# NixieMainboard.net
KiCad netlist of a schematic drawn in EAGLE
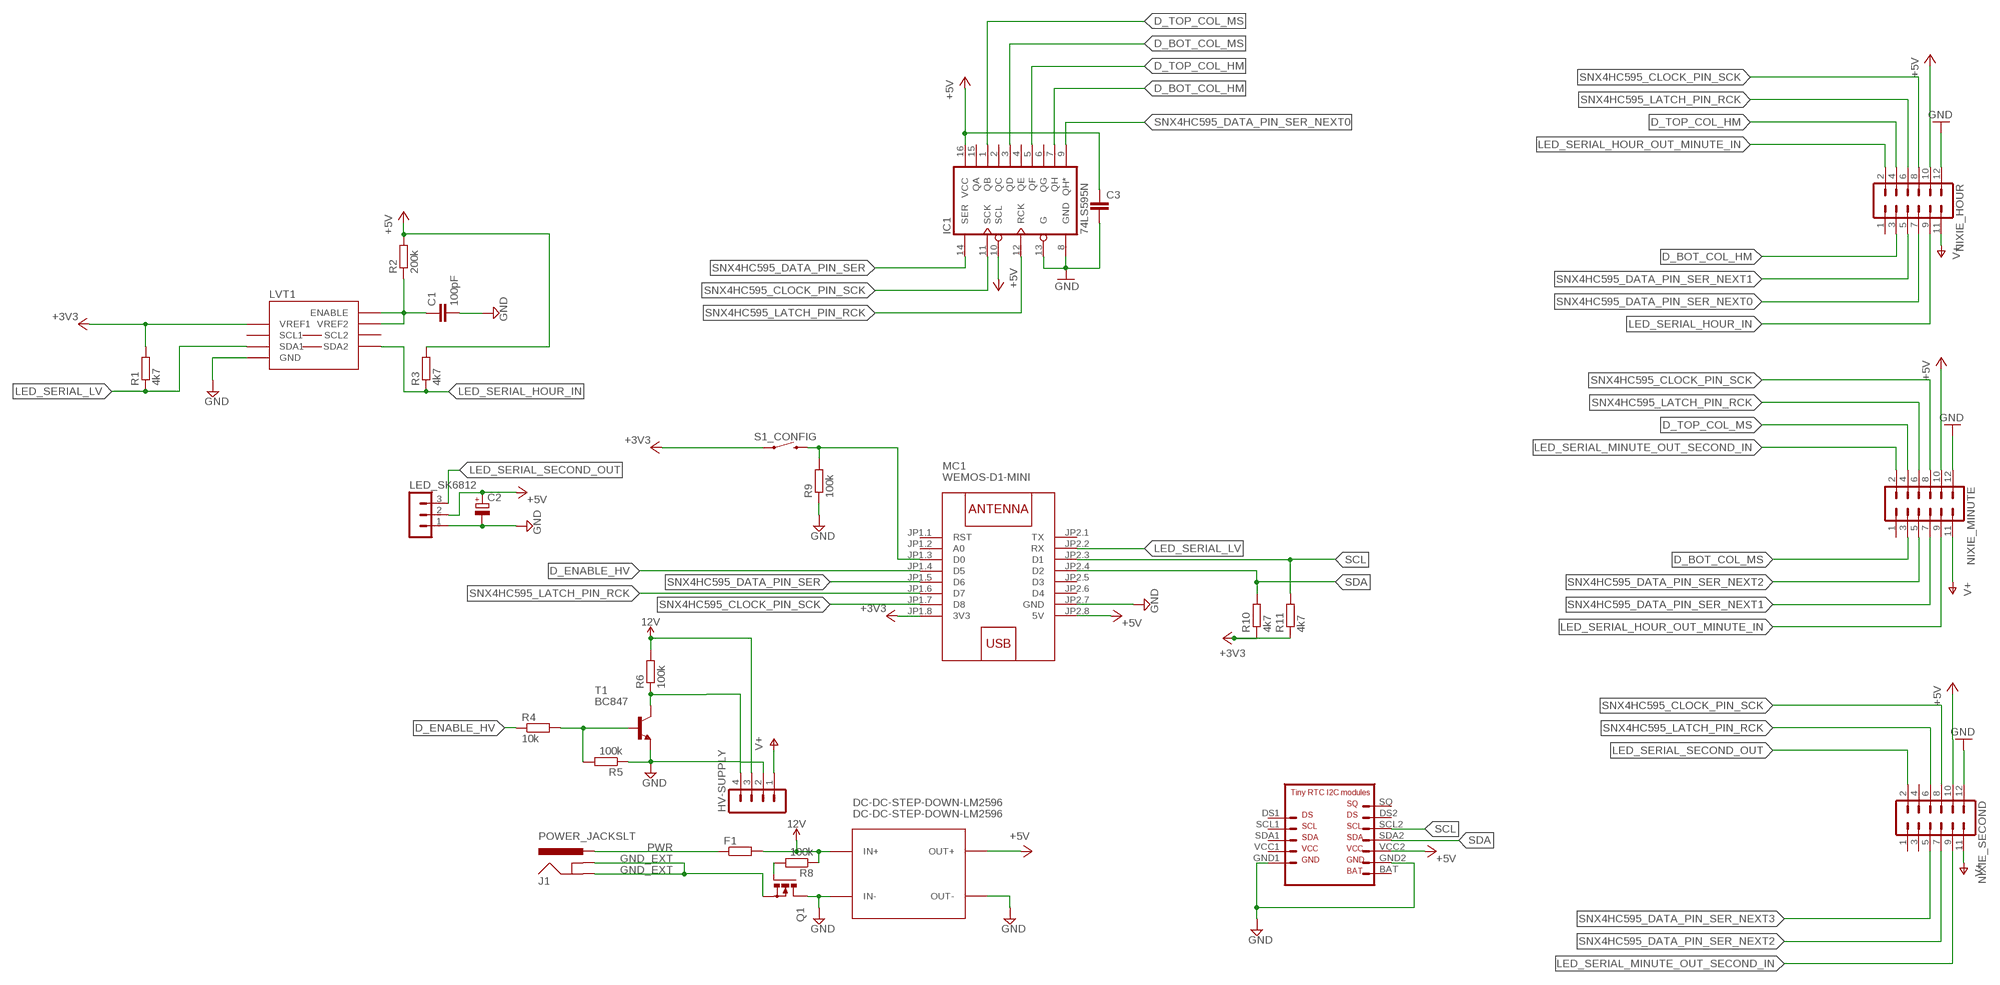
[diagram p0: schematic, sheet 1]

(export (version "E")
  (design (tool "Eeschema 10.0.6"))
  (components
    (comp (ref "C1")
      (value "100pF")
      (footprint "eagle-import:C0805")
      (libsource (lib "eagle-import") (part "C-EUC0805"))
    )
    (comp (ref "C2")
      (value "CPOL-EUE5-8.5")
      (footprint "eagle-import:E5-8,5")
      (libsource (lib "eagle-import") (part "CPOL-EUE5-8.5"))
    )
    (comp (ref "C3")
      (value "C-EU050-024X044")
      (footprint "eagle-import:C050-024X044")
      (libsource (lib "eagle-import") (part "C-EU050-024X044"))
    )
    (comp (ref "DC-DC-STEP-DOWN-LM2596")
      (value "DC-DC-STEP-DOWN-LM2596")
      (footprint "eagle-import:DC-DC-STEP-DOWN-LM2596")
      (libsource (lib "eagle-import") (part "DC-DC-STEP-DOWN-LM2596"))
    )
    (comp (ref "F1")
      (value "R-EU_R2512W")
      (footprint "eagle-import:R2512W")
      (libsource (lib "eagle-import") (part "R-EU_R2512W"))
    )
    (comp (ref "HV-SUPPLY")
      (value "MA04-1")
      (footprint "eagle-import:MA04-1")
      (libsource (lib "eagle-import") (part "MA04-1"))
    )
    (comp (ref "IC1")
      (value "74LS595N")
      (footprint "eagle-import:DIL16")
      (libsource (lib "eagle-import") (part "74595NLS"))
    )
    (comp (ref "J1")
      (value "POWER_JACKSLT")
      (footprint "eagle-import:POWER_JACK_SLOT")
      (libsource (lib "eagle-import") (part "POWER_JACKSLT"))
    )
    (comp (ref "LED_SK6812")
      (value "MA03-1")
      (footprint "eagle-import:MA03-1")
      (libsource (lib "eagle-import") (part "MA03-1"))
    )
    (comp (ref "LVT1")
      (value "IC2_LEVEL_TRANSLATER")
      (footprint "eagle-import:SOIC-8")
      (libsource (lib "eagle-import") (part "IC2_LEVEL_TRANSLATER"))
    )
    (comp (ref "MC1")
      (value "WEMOS-D1-MINI")
      (footprint "eagle-import:WEMOS-D1-MINI")
      (libsource (lib "eagle-import") (part "WEMOS-D1-MINI"))
    )
    (comp (ref "NIXIE_HOUR")
      (value "MA06-2")
      (footprint "eagle-import:MA06-2")
      (libsource (lib "eagle-import") (part "MA06-2"))
    )
    (comp (ref "NIXIE_MINUTE")
      (value "MA06-2")
      (footprint "eagle-import:MA06-2")
      (libsource (lib "eagle-import") (part "MA06-2"))
    )
    (comp (ref "NIXIE_SECOND")
      (value "MA06-2")
      (footprint "eagle-import:MA06-2")
      (libsource (lib "eagle-import") (part "MA06-2"))
    )
    (comp (ref "Q1")
      (value "PMOSFET_NTO220BV")
      (footprint "eagle-import:TO220BV")
      (libsource (lib "eagle-import") (part "PMOSFET_NTO220BV"))
    )
    (comp (ref "R1")
      (value "4k7")
      (footprint "eagle-import:R0805")
      (libsource (lib "eagle-import") (part "R-EU_R0805"))
    )
    (comp (ref "R2")
      (value "200k")
      (footprint "eagle-import:R0805")
      (libsource (lib "eagle-import") (part "R-EU_R0805"))
    )
    (comp (ref "R3")
      (value "4k7")
      (footprint "eagle-import:R0805")
      (libsource (lib "eagle-import") (part "R-EU_R0805"))
    )
    (comp (ref "R4")
      (value "10k")
      (footprint "eagle-import:R0805")
      (libsource (lib "eagle-import") (part "R-EU_R0805"))
    )
    (comp (ref "R5")
      (value "100k")
      (footprint "eagle-import:R0805")
      (libsource (lib "eagle-import") (part "R-EU_R0805"))
    )
    (comp (ref "R6")
      (value "100k")
      (footprint "eagle-import:R0805")
      (libsource (lib "eagle-import") (part "R-EU_R0805"))
    )
    (comp (ref "R8")
      (value "100k")
      (footprint "eagle-import:R0805")
      (libsource (lib "eagle-import") (part "R-EU_R0805"))
    )
    (comp (ref "R9")
      (value "100k")
      (footprint "eagle-import:R0805")
      (libsource (lib "eagle-import") (part "R-EU_R0805"))
    )
    (comp (ref "R10")
      (value "4k7")
      (footprint "eagle-import:R0805")
      (libsource (lib "eagle-import") (part "R-EU_R0805"))
    )
    (comp (ref "R11")
      (value "4k7")
      (footprint "eagle-import:R0805")
      (libsource (lib "eagle-import") (part "R-EU_R0805"))
    )
    (comp (ref "RTC1")
      (value "RTC")
      (footprint "eagle-import:RTC")
      (libsource (lib "eagle-import") (part "RTC"))
    )
    (comp (ref "S1_CONFIG")
      (value "MOMENTARY-SWITCH-SPST-PTH-6.0MM")
      (footprint "eagle-import:TACTILE_SWITCH_PTH_6.0MM")
      (libsource (lib "eagle-import") (part "MOMENTARY-SWITCH-SPST-PTH-6.0MM"))
    )
    (comp (ref "T1")
      (value "BC847")
      (footprint "eagle-import:SOT23")
      (libsource (lib "eagle-import") (part "BC847"))
    )
  )
  (nets
    (net (code "1") (name "+3V3") (class "Default")
      (node (ref "LVT1") (pin "1") (pinfunction "VREF1_1") (pintype "power_in"))
      (node (ref "MC1") (pin "JP1.8") (pinfunction "3V3_JP1.8") (pintype "power_in"))
      (node (ref "R1") (pin "2") (pinfunction "2_2") (pintype "passive"))
      (node (ref "R10") (pin "1") (pinfunction "1_1") (pintype "passive"))
      (node (ref "R11") (pin "1") (pinfunction "1_1") (pintype "passive"))
      (node (ref "S1_CONFIG") (pin "1") (pinfunction "1_1") (pintype "passive"))
    )
    (net (code "2") (name "+5V") (class "Default")
      (node (ref "C2") (pin "+") (pinfunction "+_+") (pintype "passive"))
      (node (ref "C3") (pin "1") (pinfunction "1_1") (pintype "passive"))
      (node (ref "DC-DC-STEP-DOWN-LM2596") (pin "OUT+") (pinfunction "OUT+_OUT+") (pintype "bidirectional"))
      (node (ref "IC1") (pin "10") (pinfunction "SCL_10") (pintype "input"))
      (node (ref "IC1") (pin "16") (pinfunction "VCC_16") (pintype "power_in"))
      (node (ref "LED_SK6812") (pin "2") (pinfunction "2_2") (pintype "passive"))
      (node (ref "MC1") (pin "JP2.8") (pinfunction "5V_JP2.8") (pintype "power_in"))
      (node (ref "NIXIE_HOUR") (pin "10") (pinfunction "10_10") (pintype "passive"))
      (node (ref "NIXIE_MINUTE") (pin "10") (pinfunction "10_10") (pintype "passive"))
      (node (ref "NIXIE_SECOND") (pin "10") (pinfunction "10_10") (pintype "passive"))
      (node (ref "R2") (pin "2") (pinfunction "2_2") (pintype "passive"))
      (node (ref "R3") (pin "2") (pinfunction "2_2") (pintype "passive"))
      (node (ref "RTC1") (pin "VCC2") (pinfunction "VCC2_VCC2") (pintype "passive"))
    )
    (net (code "3") (name "/GND_EXT") (class "Default")
      (node (ref "J1") (pin "GND@1") (pinfunction "GNDBREAK_GND@1") (pintype "bidirectional"))
      (node (ref "J1") (pin "GND@2") (pinfunction "GND_GND@2") (pintype "bidirectional"))
      (node (ref "Q1") (pin "S") (pinfunction "S_S") (pintype "passive"))
    )
    (net (code "4") (name "/PWR") (class "Default")
      (node (ref "F1") (pin "1") (pinfunction "1_1") (pintype "passive"))
      (node (ref "J1") (pin "PWR") (pinfunction "PWR_PWR") (pintype "bidirectional"))
    )
    (net (code "5") (name "12V") (class "Default")
      (node (ref "DC-DC-STEP-DOWN-LM2596") (pin "IN+") (pinfunction "IN+_IN+") (pintype "bidirectional"))
      (node (ref "F1") (pin "2") (pinfunction "2_2") (pintype "passive"))
      (node (ref "HV-SUPPLY") (pin "3") (pinfunction "3_3") (pintype "passive"))
      (node (ref "R6") (pin "2") (pinfunction "2_2") (pintype "passive"))
      (node (ref "R8") (pin "1") (pinfunction "1_1") (pintype "passive"))
    )
    (net (code "6") (name "D_BOT_COL_HM") (class "Default")
      (node (ref "IC1") (pin "7") (pinfunction "QH_7") (pintype "tri_state"))
      (node (ref "NIXIE_HOUR") (pin "3") (pinfunction "3_3") (pintype "passive"))
    )
    (net (code "7") (name "D_BOT_COL_MS") (class "Default")
      (node (ref "IC1") (pin "3") (pinfunction "QD_3") (pintype "tri_state"))
      (node (ref "NIXIE_MINUTE") (pin "3") (pinfunction "3_3") (pintype "passive"))
    )
    (net (code "8") (name "D_ENABLE_HV") (class "Default")
      (node (ref "MC1") (pin "JP1.4") (pinfunction "D5_JP1.4") (pintype "bidirectional"))
      (node (ref "R4") (pin "1") (pinfunction "1_1") (pintype "passive"))
    )
    (net (code "9") (name "D_TOP_COL_HM") (class "Default")
      (node (ref "IC1") (pin "5") (pinfunction "QF_5") (pintype "tri_state"))
      (node (ref "NIXIE_HOUR") (pin "4") (pinfunction "4_4") (pintype "passive"))
    )
    (net (code "10") (name "D_TOP_COL_MS") (class "Default")
      (node (ref "IC1") (pin "1") (pinfunction "QB_1") (pintype "tri_state"))
      (node (ref "NIXIE_MINUTE") (pin "4") (pinfunction "4_4") (pintype "passive"))
    )
    (net (code "11") (name "GND") (class "Default")
      (node (ref "C1") (pin "2") (pinfunction "2_2") (pintype "passive"))
      (node (ref "C2") (pin "-") (pinfunction "-_-") (pintype "passive"))
      (node (ref "C3") (pin "2") (pinfunction "2_2") (pintype "passive"))
      (node (ref "DC-DC-STEP-DOWN-LM2596") (pin "IN-") (pinfunction "IN-_IN-") (pintype "bidirectional"))
      (node (ref "DC-DC-STEP-DOWN-LM2596") (pin "OUT-") (pinfunction "OUT-_OUT-") (pintype "bidirectional"))
      (node (ref "HV-SUPPLY") (pin "2") (pinfunction "2_2") (pintype "passive"))
      (node (ref "IC1") (pin "13") (pinfunction "G_13") (pintype "input"))
      (node (ref "IC1") (pin "8") (pinfunction "GND_8") (pintype "power_in"))
      (node (ref "LED_SK6812") (pin "1") (pinfunction "1_1") (pintype "passive"))
      (node (ref "LVT1") (pin "4") (pinfunction "GND_4") (pintype "power_in"))
      (node (ref "MC1") (pin "JP2.7") (pinfunction "GND_JP2.7") (pintype "power_in"))
      (node (ref "NIXIE_HOUR") (pin "12") (pinfunction "12_12") (pintype "passive"))
      (node (ref "NIXIE_MINUTE") (pin "12") (pinfunction "12_12") (pintype "passive"))
      (node (ref "NIXIE_SECOND") (pin "12") (pinfunction "12_12") (pintype "passive"))
      (node (ref "Q1") (pin "D") (pinfunction "D_D") (pintype "passive"))
      (node (ref "R5") (pin "1") (pinfunction "1_1") (pintype "passive"))
      (node (ref "R9") (pin "1") (pinfunction "1_1") (pintype "passive"))
      (node (ref "RTC1") (pin "GND1") (pinfunction "GND1_GND1") (pintype "passive"))
      (node (ref "RTC1") (pin "GND2") (pinfunction "GND2_GND2") (pintype "passive"))
      (node (ref "T1") (pin "2") (pinfunction "E_2") (pintype "passive"))
    )
    (net (code "12") (name "LED_SERIAL_HOUR_IN") (class "Default")
      (node (ref "LVT1") (pin "5") (pinfunction "SDA2_5") (pintype "bidirectional"))
      (node (ref "NIXIE_HOUR") (pin "9") (pinfunction "9_9") (pintype "passive"))
      (node (ref "R3") (pin "1") (pinfunction "1_1") (pintype "passive"))
    )
    (net (code "13") (name "LED_SERIAL_HOUR_OUT_MINUTE_IN") (class "Default")
      (node (ref "NIXIE_HOUR") (pin "2") (pinfunction "2_2") (pintype "passive"))
      (node (ref "NIXIE_MINUTE") (pin "9") (pinfunction "9_9") (pintype "passive"))
    )
    (net (code "14") (name "LED_SERIAL_LV") (class "Default")
      (node (ref "LVT1") (pin "3") (pinfunction "SDA1_3") (pintype "bidirectional"))
      (node (ref "MC1") (pin "JP2.2") (pinfunction "RX_JP2.2") (pintype "bidirectional"))
      (node (ref "R1") (pin "1") (pinfunction "1_1") (pintype "passive"))
    )
    (net (code "15") (name "LED_SERIAL_MINUTE_OUT_SECOND_IN") (class "Default")
      (node (ref "NIXIE_MINUTE") (pin "2") (pinfunction "2_2") (pintype "passive"))
      (node (ref "NIXIE_SECOND") (pin "9") (pinfunction "9_9") (pintype "passive"))
    )
    (net (code "16") (name "LED_SERIAL_SECOND_OUT") (class "Default")
      (node (ref "LED_SK6812") (pin "3") (pinfunction "3_3") (pintype "passive"))
      (node (ref "NIXIE_SECOND") (pin "2") (pinfunction "2_2") (pintype "passive"))
    )
    (net (code "17") (name "Net-(LVT1-ENABLE)") (class "Default")
      (node (ref "C1") (pin "1") (pinfunction "1_1") (pintype "passive"))
      (node (ref "LVT1") (pin "7") (pinfunction "VREF2_7") (pintype "power_in"))
      (node (ref "LVT1") (pin "8") (pinfunction "ENABLE_8") (pintype "input"))
      (node (ref "R2") (pin "1") (pinfunction "1_1") (pintype "passive"))
    )
    (net (code "18") (name "Net-(MC1-D0)") (class "Default")
      (node (ref "MC1") (pin "JP1.3") (pinfunction "D0_JP1.3") (pintype "bidirectional"))
      (node (ref "R9") (pin "2") (pinfunction "2_2") (pintype "passive"))
      (node (ref "S1_CONFIG") (pin "3") (pinfunction "2_3") (pintype "passive"))
    )
    (net (code "19") (name "Net-(Q1-PadG)") (class "Default")
      (node (ref "Q1") (pin "G") (pinfunction "G_G") (pintype "passive"))
      (node (ref "R8") (pin "2") (pinfunction "2_2") (pintype "passive"))
    )
    (net (code "20") (name "Net-(T1-B)") (class "Default")
      (node (ref "R4") (pin "2") (pinfunction "2_2") (pintype "passive"))
      (node (ref "R5") (pin "2") (pinfunction "2_2") (pintype "passive"))
      (node (ref "T1") (pin "1") (pinfunction "B_1") (pintype "passive"))
    )
    (net (code "21") (name "Net-(T1-C)") (class "Default")
      (node (ref "HV-SUPPLY") (pin "4") (pinfunction "4_4") (pintype "passive"))
      (node (ref "R6") (pin "1") (pinfunction "1_1") (pintype "passive"))
      (node (ref "T1") (pin "3") (pinfunction "C_3") (pintype "passive"))
    )
    (net (code "22") (name "SCL") (class "Default")
      (node (ref "MC1") (pin "JP2.3") (pinfunction "D1_JP2.3") (pintype "bidirectional"))
      (node (ref "R11") (pin "2") (pinfunction "2_2") (pintype "passive"))
      (node (ref "RTC1") (pin "SCL2") (pinfunction "SCL2_SCL2") (pintype "passive"))
    )
    (net (code "23") (name "SDA") (class "Default")
      (node (ref "MC1") (pin "JP2.4") (pinfunction "D2_JP2.4") (pintype "bidirectional"))
      (node (ref "R10") (pin "2") (pinfunction "2_2") (pintype "passive"))
      (node (ref "RTC1") (pin "SDA2") (pinfunction "SDA2_SDA2") (pintype "passive"))
    )
    (net (code "24") (name "SNX4HC595_CLOCK_PIN_SCK") (class "Default")
      (node (ref "IC1") (pin "11") (pinfunction "SCK_11") (pintype "input"))
      (node (ref "MC1") (pin "JP1.7") (pinfunction "D8_JP1.7") (pintype "bidirectional"))
      (node (ref "NIXIE_HOUR") (pin "8") (pinfunction "8_8") (pintype "passive"))
      (node (ref "NIXIE_MINUTE") (pin "8") (pinfunction "8_8") (pintype "passive"))
      (node (ref "NIXIE_SECOND") (pin "8") (pinfunction "8_8") (pintype "passive"))
    )
    (net (code "25") (name "SNX4HC595_DATA_PIN_SER") (class "Default")
      (node (ref "IC1") (pin "14") (pinfunction "SER_14") (pintype "input"))
      (node (ref "MC1") (pin "JP1.5") (pinfunction "D6_JP1.5") (pintype "bidirectional"))
    )
    (net (code "26") (name "SNX4HC595_DATA_PIN_SER_NEXT0") (class "Default")
      (node (ref "IC1") (pin "9") (pinfunction "QH*_9") (pintype "tri_state"))
      (node (ref "NIXIE_HOUR") (pin "7") (pinfunction "7_7") (pintype "passive"))
    )
    (net (code "27") (name "SNX4HC595_DATA_PIN_SER_NEXT1") (class "Default")
      (node (ref "NIXIE_HOUR") (pin "5") (pinfunction "5_5") (pintype "passive"))
      (node (ref "NIXIE_MINUTE") (pin "7") (pinfunction "7_7") (pintype "passive"))
    )
    (net (code "28") (name "SNX4HC595_DATA_PIN_SER_NEXT2") (class "Default")
      (node (ref "NIXIE_MINUTE") (pin "5") (pinfunction "5_5") (pintype "passive"))
      (node (ref "NIXIE_SECOND") (pin "7") (pinfunction "7_7") (pintype "passive"))
    )
    (net (code "29") (name "SNX4HC595_DATA_PIN_SER_NEXT3") (class "Default")
      (node (ref "NIXIE_SECOND") (pin "5") (pinfunction "5_5") (pintype "passive"))
    )
    (net (code "30") (name "SNX4HC595_LATCH_PIN_RCK") (class "Default")
      (node (ref "IC1") (pin "12") (pinfunction "RCK_12") (pintype "input"))
      (node (ref "MC1") (pin "JP1.6") (pinfunction "D7_JP1.6") (pintype "bidirectional"))
      (node (ref "NIXIE_HOUR") (pin "6") (pinfunction "6_6") (pintype "passive"))
      (node (ref "NIXIE_MINUTE") (pin "6") (pinfunction "6_6") (pintype "passive"))
      (node (ref "NIXIE_SECOND") (pin "6") (pinfunction "6_6") (pintype "passive"))
    )
    (net (code "31") (name "V+") (class "Default")
      (node (ref "HV-SUPPLY") (pin "1") (pinfunction "1_1") (pintype "passive"))
      (node (ref "NIXIE_HOUR") (pin "11") (pinfunction "11_11") (pintype "passive"))
      (node (ref "NIXIE_MINUTE") (pin "11") (pinfunction "11_11") (pintype "passive"))
      (node (ref "NIXIE_SECOND") (pin "11") (pinfunction "11_11") (pintype "passive"))
    )
    (net (code "32") (name "unconnected-(IC1-QA-Pad15)") (class "Default")
      (node (ref "IC1") (pin "15") (pinfunction "QA_15") (pintype "tri_state"))
    )
    (net (code "33") (name "unconnected-(IC1-QC-Pad2)") (class "Default")
      (node (ref "IC1") (pin "2") (pinfunction "QC_2") (pintype "tri_state"))
    )
    (net (code "34") (name "unconnected-(IC1-QE-Pad4)") (class "Default")
      (node (ref "IC1") (pin "4") (pinfunction "QE_4") (pintype "tri_state"))
    )
    (net (code "35") (name "unconnected-(IC1-QG-Pad6)") (class "Default")
      (node (ref "IC1") (pin "6") (pinfunction "QG_6") (pintype "tri_state"))
    )
    (net (code "36") (name "unconnected-(LVT1-SCL1-Pad2)") (class "Default")
      (node (ref "LVT1") (pin "2") (pinfunction "SCL1_2") (pintype "bidirectional"))
    )
    (net (code "37") (name "unconnected-(LVT1-SCL2-Pad6)") (class "Default")
      (node (ref "LVT1") (pin "6") (pinfunction "SCL2_6") (pintype "bidirectional"))
    )
    (net (code "38") (name "unconnected-(MC1-A0-PadJP1.2)") (class "Default")
      (node (ref "MC1") (pin "JP1.2") (pinfunction "A0_JP1.2") (pintype "bidirectional"))
    )
    (net (code "39") (name "unconnected-(MC1-D3-PadJP2.5)") (class "Default")
      (node (ref "MC1") (pin "JP2.5") (pinfunction "D3_JP2.5") (pintype "bidirectional"))
    )
    (net (code "40") (name "unconnected-(MC1-D4-PadJP2.6)") (class "Default")
      (node (ref "MC1") (pin "JP2.6") (pinfunction "D4_JP2.6") (pintype "bidirectional"))
    )
    (net (code "41") (name "unconnected-(MC1-RST-PadJP1.1)") (class "Default")
      (node (ref "MC1") (pin "JP1.1") (pinfunction "RST_JP1.1") (pintype "bidirectional"))
    )
    (net (code "42") (name "unconnected-(MC1-TX-PadJP2.1)") (class "Default")
      (node (ref "MC1") (pin "JP2.1") (pinfunction "TX_JP2.1") (pintype "bidirectional"))
    )
    (net (code "43") (name "unconnected-(NIXIE_HOUR-Pad1)") (class "Default")
      (node (ref "NIXIE_HOUR") (pin "1") (pinfunction "1_1") (pintype "passive"))
    )
    (net (code "44") (name "unconnected-(NIXIE_MINUTE-Pad1)") (class "Default")
      (node (ref "NIXIE_MINUTE") (pin "1") (pinfunction "1_1") (pintype "passive"))
    )
    (net (code "45") (name "unconnected-(NIXIE_SECOND-Pad1)") (class "Default")
      (node (ref "NIXIE_SECOND") (pin "1") (pinfunction "1_1") (pintype "passive"))
    )
    (net (code "46") (name "unconnected-(NIXIE_SECOND-Pad3)") (class "Default")
      (node (ref "NIXIE_SECOND") (pin "3") (pinfunction "3_3") (pintype "passive"))
    )
    (net (code "47") (name "unconnected-(NIXIE_SECOND-Pad4)") (class "Default")
      (node (ref "NIXIE_SECOND") (pin "4") (pinfunction "4_4") (pintype "passive"))
    )
    (net (code "48") (name "unconnected-(RTC1-PadBAT)") (class "Default")
      (node (ref "RTC1") (pin "BAT") (pinfunction "BAT_BAT") (pintype "passive"))
    )
    (net (code "49") (name "unconnected-(RTC1-PadDS1)") (class "Default")
      (node (ref "RTC1") (pin "DS1") (pinfunction "DS1_DS1") (pintype "passive"))
    )
    (net (code "50") (name "unconnected-(RTC1-PadDS2)") (class "Default")
      (node (ref "RTC1") (pin "DS2") (pinfunction "DS2_DS2") (pintype "passive"))
    )
    (net (code "51") (name "unconnected-(RTC1-PadSCL1)") (class "Default")
      (node (ref "RTC1") (pin "SCL1") (pinfunction "SCL1_SCL1") (pintype "passive"))
    )
    (net (code "52") (name "unconnected-(RTC1-PadSDA1)") (class "Default")
      (node (ref "RTC1") (pin "SDA1") (pinfunction "SDA1_SDA1") (pintype "passive"))
    )
    (net (code "53") (name "unconnected-(RTC1-PadSQ)") (class "Default")
      (node (ref "RTC1") (pin "SQ") (pinfunction "SQ_SQ") (pintype "passive"))
    )
    (net (code "54") (name "unconnected-(RTC1-PadVCC1)") (class "Default")
      (node (ref "RTC1") (pin "VCC1") (pinfunction "VCC1_VCC1") (pintype "passive"))
    )
  )
)
